# attenuverter.net
KiCad netlist of a schematic drawn in EAGLE
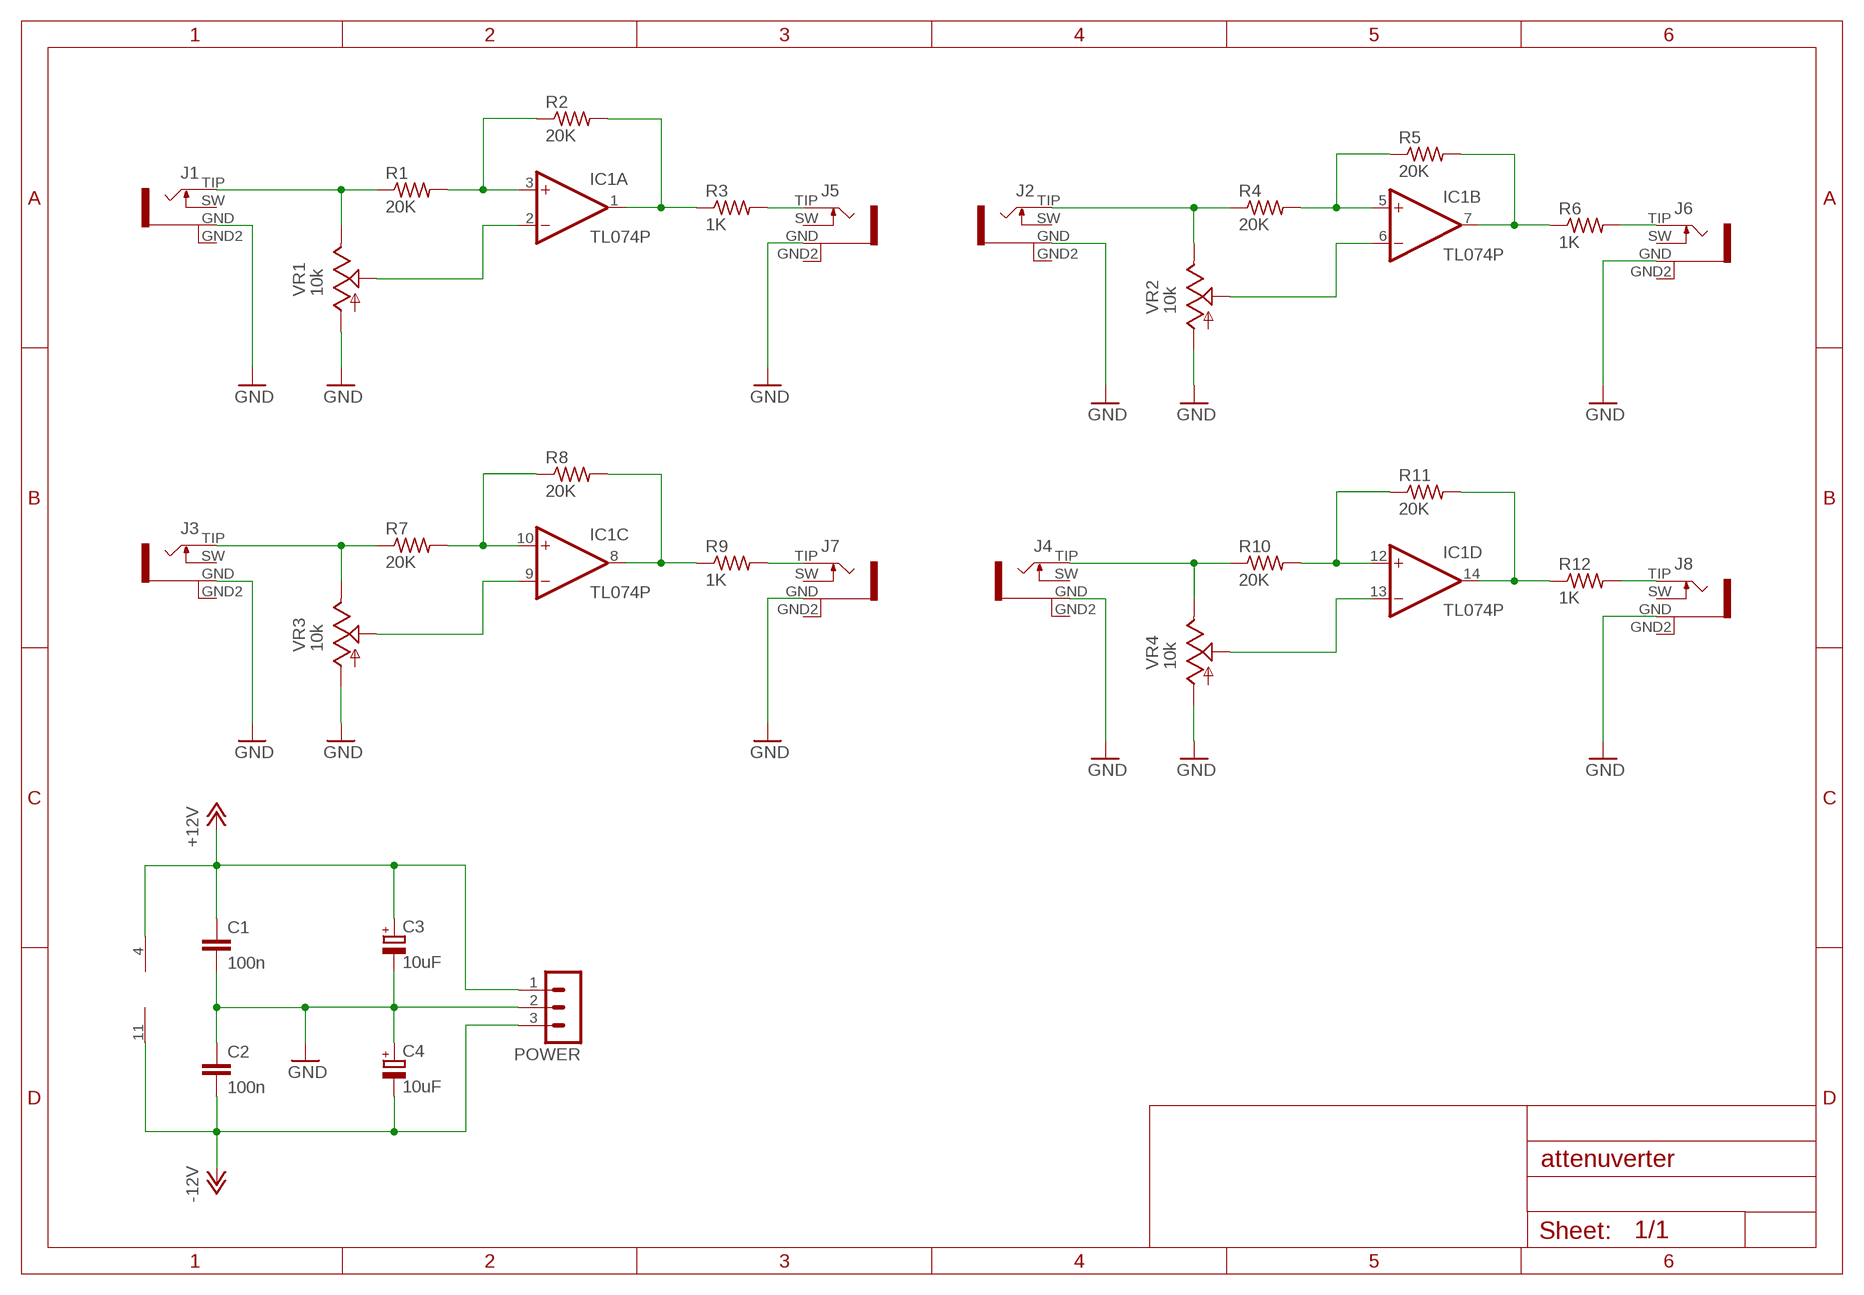
[diagram p0: schematic, sheet 1]

(export (version "E")
  (design (tool "Eeschema 10.0.6"))
  (components
    (comp (ref "C1")
      (value "100n")
      (footprint "eagle-import:C025-025X050")
      (libsource (lib "eagle-import") (part "C-EU025-025X050"))
    )
    (comp (ref "C2")
      (value "100n")
      (footprint "eagle-import:C025-025X050")
      (libsource (lib "eagle-import") (part "C-EU025-025X050"))
    )
    (comp (ref "C3")
      (value "10uF")
      (footprint "eagle-import:E2,5-6E")
      (libsource (lib "eagle-import") (part "CPOL-EUE2,5-6E"))
    )
    (comp (ref "C4")
      (value "10uF")
      (footprint "eagle-import:E2,5-6E")
      (libsource (lib "eagle-import") (part "CPOL-EUE2,5-6E"))
    )
    (comp (ref "IC1")
      (value "TL074P")
      (footprint "eagle-import:DIL14")
      (libsource (lib "eagle-import") (part "TL074P"))
    )
    (comp (ref "J1")
      (value "PJ301WQP")
      (footprint "eagle-import:THONK_JACK_P")
      (libsource (lib "eagle-import") (part "PJ301WQP"))
    )
    (comp (ref "J2")
      (value "PJ301WQP")
      (footprint "eagle-import:THONK_JACK_P")
      (libsource (lib "eagle-import") (part "PJ301WQP"))
    )
    (comp (ref "J3")
      (value "PJ301WQP")
      (footprint "eagle-import:THONK_JACK_P")
      (libsource (lib "eagle-import") (part "PJ301WQP"))
    )
    (comp (ref "J4")
      (value "PJ301WQP")
      (footprint "eagle-import:THONK_JACK_P")
      (libsource (lib "eagle-import") (part "PJ301WQP"))
    )
    (comp (ref "J5")
      (value "PJ301WQP")
      (footprint "eagle-import:THONK_JACK_P")
      (libsource (lib "eagle-import") (part "PJ301WQP"))
    )
    (comp (ref "J6")
      (value "PJ301WQP")
      (footprint "eagle-import:THONK_JACK_P")
      (libsource (lib "eagle-import") (part "PJ301WQP"))
    )
    (comp (ref "J7")
      (value "PJ301WQP")
      (footprint "eagle-import:THONK_JACK_P")
      (libsource (lib "eagle-import") (part "PJ301WQP"))
    )
    (comp (ref "J8")
      (value "PJ301WQP")
      (footprint "eagle-import:THONK_JACK_P")
      (libsource (lib "eagle-import") (part "PJ301WQP"))
    )
    (comp (ref "POWER")
      (value "MA03-1")
      (footprint "eagle-import:MA03-1")
      (libsource (lib "eagle-import") (part "MA03-1"))
    )
    (comp (ref "R1")
      (value "20K")
      (footprint "eagle-import:0207_10")
      (libsource (lib "eagle-import") (part "R-US_0207/10"))
    )
    (comp (ref "R2")
      (value "20K")
      (footprint "eagle-import:0207_10")
      (libsource (lib "eagle-import") (part "R-US_0207/10"))
    )
    (comp (ref "R3")
      (value "1K")
      (footprint "eagle-import:0207_10")
      (libsource (lib "eagle-import") (part "R-US_0207/10"))
    )
    (comp (ref "R4")
      (value "20K")
      (footprint "eagle-import:0207_10")
      (libsource (lib "eagle-import") (part "R-US_0207/10"))
    )
    (comp (ref "R5")
      (value "20K")
      (footprint "eagle-import:0207_10")
      (libsource (lib "eagle-import") (part "R-US_0207/10"))
    )
    (comp (ref "R6")
      (value "1K")
      (footprint "eagle-import:0207_10")
      (libsource (lib "eagle-import") (part "R-US_0207/10"))
    )
    (comp (ref "R7")
      (value "20K")
      (footprint "eagle-import:0207_10")
      (libsource (lib "eagle-import") (part "R-US_0207/10"))
    )
    (comp (ref "R8")
      (value "20K")
      (footprint "eagle-import:0207_10")
      (libsource (lib "eagle-import") (part "R-US_0207/10"))
    )
    (comp (ref "R9")
      (value "1K")
      (footprint "eagle-import:0207_10")
      (libsource (lib "eagle-import") (part "R-US_0207/10"))
    )
    (comp (ref "R10")
      (value "20K")
      (footprint "eagle-import:0207_10")
      (libsource (lib "eagle-import") (part "R-US_0207/10"))
    )
    (comp (ref "R11")
      (value "20K")
      (footprint "eagle-import:0207_10")
      (libsource (lib "eagle-import") (part "R-US_0207/10"))
    )
    (comp (ref "R12")
      (value "1K")
      (footprint "eagle-import:0207_10")
      (libsource (lib "eagle-import") (part "R-US_0207/10"))
    )
    (comp (ref "VR1")
      (value "10k")
      (footprint "eagle-import:9MM_SNAP-IN_POT")
      (libsource (lib "eagle-import") (part "9MM_SNAP-IN_POT_"))
    )
    (comp (ref "VR2")
      (value "10k")
      (footprint "eagle-import:9MM_SNAP-IN_POT")
      (libsource (lib "eagle-import") (part "9MM_SNAP-IN_POT_"))
    )
    (comp (ref "VR3")
      (value "10k")
      (footprint "eagle-import:9MM_SNAP-IN_POT")
      (libsource (lib "eagle-import") (part "9MM_SNAP-IN_POT_"))
    )
    (comp (ref "VR4")
      (value "10k")
      (footprint "eagle-import:9MM_SNAP-IN_POT")
      (libsource (lib "eagle-import") (part "9MM_SNAP-IN_POT_"))
    )
  )
  (nets
    (net (code "1") (name "+12V") (class "Default")
      (node (ref "C1") (pin "1") (pinfunction "1_1") (pintype "passive"))
      (node (ref "C3") (pin "+") (pinfunction "+_+") (pintype "passive"))
      (node (ref "IC1") (pin "4") (pinfunction "V+_4") (pintype "power_in"))
      (node (ref "POWER") (pin "1") (pinfunction "1_1") (pintype "passive"))
    )
    (net (code "2") (name "-12V") (class "Default")
      (node (ref "C2") (pin "2") (pinfunction "2_2") (pintype "passive"))
      (node (ref "C4") (pin "-") (pinfunction "-_-") (pintype "passive"))
      (node (ref "IC1") (pin "11") (pinfunction "V-_11") (pintype "power_in"))
      (node (ref "POWER") (pin "3") (pinfunction "3_3") (pintype "passive"))
    )
    (net (code "3") (name "GND") (class "Default")
      (node (ref "C1") (pin "2") (pinfunction "2_2") (pintype "passive"))
      (node (ref "C2") (pin "1") (pinfunction "1_1") (pintype "passive"))
      (node (ref "C3") (pin "-") (pinfunction "-_-") (pintype "passive"))
      (node (ref "C4") (pin "+") (pinfunction "+_+") (pintype "passive"))
      (node (ref "J1") (pin "GND") (pinfunction "1_GND") (pintype "passive"))
      (node (ref "J2") (pin "GND") (pinfunction "1_GND") (pintype "passive"))
      (node (ref "J3") (pin "GND") (pinfunction "1_GND") (pintype "passive"))
      (node (ref "J4") (pin "GND") (pinfunction "1_GND") (pintype "passive"))
      (node (ref "J5") (pin "GND") (pinfunction "1_GND") (pintype "passive"))
      (node (ref "J6") (pin "GND") (pinfunction "1_GND") (pintype "passive"))
      (node (ref "J7") (pin "GND") (pinfunction "1_GND") (pintype "passive"))
      (node (ref "J8") (pin "GND") (pinfunction "1_GND") (pintype "passive"))
      (node (ref "POWER") (pin "2") (pinfunction "2_2") (pintype "passive"))
      (node (ref "VR1") (pin "1") (pinfunction "A_1") (pintype "passive"))
      (node (ref "VR2") (pin "1") (pinfunction "A_1") (pintype "passive"))
      (node (ref "VR3") (pin "1") (pinfunction "A_1") (pintype "passive"))
      (node (ref "VR4") (pin "1") (pinfunction "A_1") (pintype "passive"))
    )
    (net (code "4") (name "Net-(IC1A-+IN)") (class "Default")
      (node (ref "IC1") (pin "3") (pinfunction "+IN_3") (pintype "input"))
      (node (ref "R1") (pin "2") (pinfunction "2_2") (pintype "passive"))
      (node (ref "R2") (pin "1") (pinfunction "1_1") (pintype "passive"))
    )
    (net (code "5") (name "Net-(IC1A--IN)") (class "Default")
      (node (ref "IC1") (pin "2") (pinfunction "-IN_2") (pintype "input"))
      (node (ref "VR1") (pin "2") (pinfunction "S_2") (pintype "passive"))
    )
    (net (code "6") (name "Net-(IC1A-OUT)") (class "Default")
      (node (ref "IC1") (pin "1") (pinfunction "OUT_1") (pintype "output"))
      (node (ref "R2") (pin "2") (pinfunction "2_2") (pintype "passive"))
      (node (ref "R3") (pin "1") (pinfunction "1_1") (pintype "passive"))
    )
    (net (code "7") (name "Net-(IC1B-+IN)") (class "Default")
      (node (ref "IC1") (pin "5") (pinfunction "+IN_5") (pintype "input"))
      (node (ref "R4") (pin "2") (pinfunction "2_2") (pintype "passive"))
      (node (ref "R5") (pin "1") (pinfunction "1_1") (pintype "passive"))
    )
    (net (code "8") (name "Net-(IC1B--IN)") (class "Default")
      (node (ref "IC1") (pin "6") (pinfunction "-IN_6") (pintype "input"))
      (node (ref "VR2") (pin "2") (pinfunction "S_2") (pintype "passive"))
    )
    (net (code "9") (name "Net-(IC1B-OUT)") (class "Default")
      (node (ref "IC1") (pin "7") (pinfunction "OUT_7") (pintype "output"))
      (node (ref "R5") (pin "2") (pinfunction "2_2") (pintype "passive"))
      (node (ref "R6") (pin "1") (pinfunction "1_1") (pintype "passive"))
    )
    (net (code "10") (name "Net-(IC1C-+IN)") (class "Default")
      (node (ref "IC1") (pin "10") (pinfunction "+IN_10") (pintype "input"))
      (node (ref "R7") (pin "2") (pinfunction "2_2") (pintype "passive"))
      (node (ref "R8") (pin "1") (pinfunction "1_1") (pintype "passive"))
    )
    (net (code "11") (name "Net-(IC1C--IN)") (class "Default")
      (node (ref "IC1") (pin "9") (pinfunction "-IN_9") (pintype "input"))
      (node (ref "VR3") (pin "2") (pinfunction "S_2") (pintype "passive"))
    )
    (net (code "12") (name "Net-(IC1C-OUT)") (class "Default")
      (node (ref "IC1") (pin "8") (pinfunction "OUT_8") (pintype "output"))
      (node (ref "R8") (pin "2") (pinfunction "2_2") (pintype "passive"))
      (node (ref "R9") (pin "1") (pinfunction "1_1") (pintype "passive"))
    )
    (net (code "13") (name "Net-(IC1D-+IN)") (class "Default")
      (node (ref "IC1") (pin "12") (pinfunction "+IN_12") (pintype "input"))
      (node (ref "R10") (pin "2") (pinfunction "2_2") (pintype "passive"))
      (node (ref "R11") (pin "1") (pinfunction "1_1") (pintype "passive"))
    )
    (net (code "14") (name "Net-(IC1D--IN)") (class "Default")
      (node (ref "IC1") (pin "13") (pinfunction "-IN_13") (pintype "input"))
      (node (ref "VR4") (pin "2") (pinfunction "S_2") (pintype "passive"))
    )
    (net (code "15") (name "Net-(IC1D-OUT)") (class "Default")
      (node (ref "IC1") (pin "14") (pinfunction "OUT_14") (pintype "output"))
      (node (ref "R11") (pin "2") (pinfunction "2_2") (pintype "passive"))
      (node (ref "R12") (pin "1") (pinfunction "1_1") (pintype "passive"))
    )
    (net (code "16") (name "Net-(J1-2)") (class "Default")
      (node (ref "J1") (pin "TIP") (pinfunction "2_TIP") (pintype "passive"))
      (node (ref "R1") (pin "1") (pinfunction "1_1") (pintype "passive"))
      (node (ref "VR1") (pin "3") (pinfunction "E_3") (pintype "passive"))
    )
    (net (code "17") (name "Net-(J2-2)") (class "Default")
      (node (ref "J2") (pin "TIP") (pinfunction "2_TIP") (pintype "passive"))
      (node (ref "R4") (pin "1") (pinfunction "1_1") (pintype "passive"))
      (node (ref "VR2") (pin "3") (pinfunction "E_3") (pintype "passive"))
    )
    (net (code "18") (name "Net-(J3-2)") (class "Default")
      (node (ref "J3") (pin "TIP") (pinfunction "2_TIP") (pintype "passive"))
      (node (ref "R7") (pin "1") (pinfunction "1_1") (pintype "passive"))
      (node (ref "VR3") (pin "3") (pinfunction "E_3") (pintype "passive"))
    )
    (net (code "19") (name "Net-(J4-2)") (class "Default")
      (node (ref "J4") (pin "TIP") (pinfunction "2_TIP") (pintype "passive"))
      (node (ref "R10") (pin "1") (pinfunction "1_1") (pintype "passive"))
      (node (ref "VR4") (pin "3") (pinfunction "E_3") (pintype "passive"))
    )
    (net (code "20") (name "Net-(J5-2)") (class "Default")
      (node (ref "J5") (pin "TIP") (pinfunction "2_TIP") (pintype "passive"))
      (node (ref "R3") (pin "2") (pinfunction "2_2") (pintype "passive"))
    )
    (net (code "21") (name "Net-(J6-2)") (class "Default")
      (node (ref "J6") (pin "TIP") (pinfunction "2_TIP") (pintype "passive"))
      (node (ref "R6") (pin "2") (pinfunction "2_2") (pintype "passive"))
    )
    (net (code "22") (name "Net-(J7-2)") (class "Default")
      (node (ref "J7") (pin "TIP") (pinfunction "2_TIP") (pintype "passive"))
      (node (ref "R9") (pin "2") (pinfunction "2_2") (pintype "passive"))
    )
    (net (code "23") (name "Net-(J8-2)") (class "Default")
      (node (ref "J8") (pin "TIP") (pinfunction "2_TIP") (pintype "passive"))
      (node (ref "R12") (pin "2") (pinfunction "2_2") (pintype "passive"))
    )
    (net (code "24") (name "unconnected-(J1-3-PadSW)") (class "Default")
      (node (ref "J1") (pin "SW") (pinfunction "3_SW") (pintype "passive"))
    )
    (net (code "25") (name "unconnected-(J1-4-PadGND2)") (class "Default")
      (node (ref "J1") (pin "GND2") (pinfunction "4_GND2") (pintype "passive"))
    )
    (net (code "26") (name "unconnected-(J2-3-PadSW)") (class "Default")
      (node (ref "J2") (pin "SW") (pinfunction "3_SW") (pintype "passive"))
    )
    (net (code "27") (name "unconnected-(J2-4-PadGND2)") (class "Default")
      (node (ref "J2") (pin "GND2") (pinfunction "4_GND2") (pintype "passive"))
    )
    (net (code "28") (name "unconnected-(J3-3-PadSW)") (class "Default")
      (node (ref "J3") (pin "SW") (pinfunction "3_SW") (pintype "passive"))
    )
    (net (code "29") (name "unconnected-(J3-4-PadGND2)") (class "Default")
      (node (ref "J3") (pin "GND2") (pinfunction "4_GND2") (pintype "passive"))
    )
    (net (code "30") (name "unconnected-(J4-3-PadSW)") (class "Default")
      (node (ref "J4") (pin "SW") (pinfunction "3_SW") (pintype "passive"))
    )
    (net (code "31") (name "unconnected-(J4-4-PadGND2)") (class "Default")
      (node (ref "J4") (pin "GND2") (pinfunction "4_GND2") (pintype "passive"))
    )
    (net (code "32") (name "unconnected-(J5-3-PadSW)") (class "Default")
      (node (ref "J5") (pin "SW") (pinfunction "3_SW") (pintype "passive"))
    )
    (net (code "33") (name "unconnected-(J5-4-PadGND2)") (class "Default")
      (node (ref "J5") (pin "GND2") (pinfunction "4_GND2") (pintype "passive"))
    )
    (net (code "34") (name "unconnected-(J6-3-PadSW)") (class "Default")
      (node (ref "J6") (pin "SW") (pinfunction "3_SW") (pintype "passive"))
    )
    (net (code "35") (name "unconnected-(J6-4-PadGND2)") (class "Default")
      (node (ref "J6") (pin "GND2") (pinfunction "4_GND2") (pintype "passive"))
    )
    (net (code "36") (name "unconnected-(J7-3-PadSW)") (class "Default")
      (node (ref "J7") (pin "SW") (pinfunction "3_SW") (pintype "passive"))
    )
    (net (code "37") (name "unconnected-(J7-4-PadGND2)") (class "Default")
      (node (ref "J7") (pin "GND2") (pinfunction "4_GND2") (pintype "passive"))
    )
    (net (code "38") (name "unconnected-(J8-3-PadSW)") (class "Default")
      (node (ref "J8") (pin "SW") (pinfunction "3_SW") (pintype "passive"))
    )
    (net (code "39") (name "unconnected-(J8-4-PadGND2)") (class "Default")
      (node (ref "J8") (pin "GND2") (pinfunction "4_GND2") (pintype "passive"))
    )
  )
)
